# Programador_XILINX.net
KiCad netlist of a schematic drawn in Altium Designer
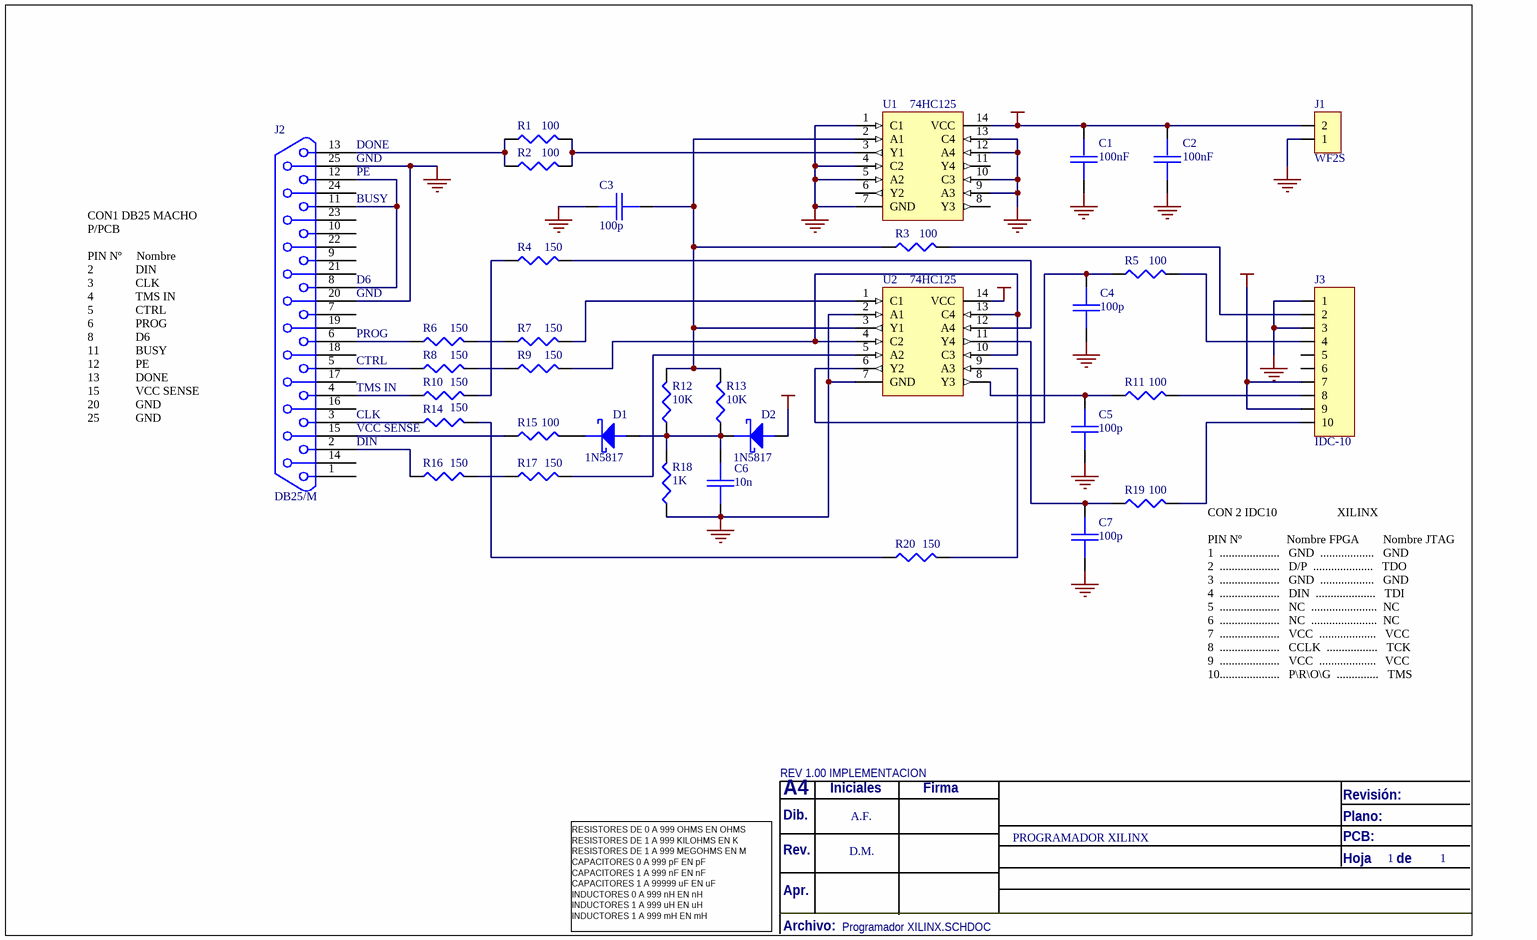
[diagram p0: Programador XILINX.SCHDOC]

(export (version "E")
  (design (tool "Eeschema 10.0.6"))
  (components
    (comp (ref "C1")
      (value "100nF")
      (footprint "0805")
      (description "CAPACITOR SMD 0805 X7R  50 V 100 nF")
      (libsource (lib "CAPACITORES SMD0805") (part "100n"))
    )
    (comp (ref "C2")
      (value "100nF")
      (footprint "0805")
      (description "CAPACITOR SMD 0805 X7R  50 V 100 nF")
      (libsource (lib "CAPACITORES SMD0805") (part "100n"))
    )
    (comp (ref "C3")
      (value "100p")
      (footprint "CAP2.54")
      (description "CAPACITOR CERAMICO DISCO 2.54 mm  X7R  50V  100pF")
      (libsource (lib "CAPACITORES CERAMICO DISCO") (part "100p"))
    )
    (comp (ref "C4")
      (value "100p")
      (footprint "CAP2.54")
      (description "CAPACITOR CERAMICO DISCO 2.54 mm  X7R  50V  100pF")
      (libsource (lib "CAPACITORES CERAMICO DISCO") (part "100p"))
    )
    (comp (ref "C5")
      (value "100p")
      (footprint "CAP2.54")
      (description "CAPACITOR CERAMICO DISCO 2.54 mm  X7R  50V  100pF")
      (libsource (lib "CAPACITORES CERAMICO DISCO") (part "100p"))
    )
    (comp (ref "C6")
      (value "10n")
      (footprint "CAP2.54")
      (description "CAPACITOR CERAMICO DISCO 2.54 mm  X7R  50V  10nF")
      (libsource (lib "CAPACITORES CERAMICO DISCO") (part "10n"))
    )
    (comp (ref "C7")
      (value "100p")
      (footprint "CAP2.54")
      (description "CAPACITOR CERAMICO DISCO 2.54 mm  X7R  50V  100pF")
      (libsource (lib "CAPACITORES CERAMICO DISCO") (part "100p"))
    )
    (comp (ref "D1")
      (value "1N5817")
      (footprint "DO-41_300")
      (description "DIODO SCHOTTKY 1N5817 DO-41")
      (libsource (lib "DIODOS") (part "1N5817 DO-41"))
    )
    (comp (ref "D2")
      (value "1N5817")
      (footprint "DO-41_300")
      (description "DIODO SCHOTTKY 1N5817 DO-41")
      (libsource (lib "DIODOS") (part "1N5817 DO-41"))
    )
    (comp (ref "J1")
      (value "WF2S")
      (footprint "WF2S")
      (description "WF2S HEADER .100\" RECTO 2 VIAS")
      (libsource (lib "CONECTORES") (part "WF2S"))
    )
    (comp (ref "J2")
      (value "DB25/M")
      (footprint "DB25 MACHO 90º")
      (description "DB25M CONECTOR D SUBMINIATURA 12 VIAS MACHO CABLE")
      (libsource (lib "CONECTORES") (part "DB25/M"))
    )
    (comp (ref "J3")
      (value "IDC-10")
      (footprint "IDC10")
      (description "CONECTOR IDC MACHO PCB NO POLARIZADO PASO 2.54 mm RECTO 2X5 VIAS")
      (libsource (lib "CONECTORES") (part "IDC10"))
    )
    (comp (ref "R1")
      (value "100")
      (footprint "RES_MF1/2W_200")
      (description "RESISTOR METAL FILM 0.5 W 5% 100 OHMS")
      (libsource (lib "RESISTORES METAL FILM MEDIO WATT") (part "100"))
    )
    (comp (ref "R2")
      (value "100")
      (footprint "RES_MF1/2W_200")
      (description "RESISTOR METAL FILM 0.5 W 5% 100 OHMS")
      (libsource (lib "RESISTORES METAL FILM MEDIO WATT") (part "100"))
    )
    (comp (ref "R3")
      (value "100")
      (footprint "RES_MF1/2W_200")
      (description "RESISTOR METAL FILM 0.5 W 5% 100 OHMS")
      (libsource (lib "RESISTORES METAL FILM MEDIO WATT") (part "100"))
    )
    (comp (ref "R4")
      (value "150")
      (footprint "RES_MF1/2W_200")
      (description "RESISTOR METAL FILM 0.5 W 5% 150 OHMS")
      (libsource (lib "RESISTORES METAL FILM MEDIO WATT") (part "150"))
    )
    (comp (ref "R5")
      (value "100")
      (footprint "RES_MF1/2W_200")
      (description "RESISTOR METAL FILM 0.5 W 5% 100 OHMS")
      (libsource (lib "RESISTORES METAL FILM MEDIO WATT") (part "100"))
    )
    (comp (ref "R6")
      (value "150")
      (footprint "RES_MF1/2W_200")
      (description "RESISTOR METAL FILM 0.5 W 5% 150 OHMS")
      (libsource (lib "RESISTORES METAL FILM MEDIO WATT") (part "150"))
    )
    (comp (ref "R7")
      (value "150")
      (footprint "RES_MF1/2W_200")
      (description "RESISTOR METAL FILM 0.5 W 5% 150 OHMS")
      (libsource (lib "RESISTORES METAL FILM MEDIO WATT") (part "150"))
    )
    (comp (ref "R8")
      (value "150")
      (footprint "RES_MF1/2W_200")
      (description "RESISTOR METAL FILM 0.5 W 5% 150 OHMS")
      (libsource (lib "RESISTORES METAL FILM MEDIO WATT") (part "150"))
    )
    (comp (ref "R9")
      (value "150")
      (footprint "RES_MF1/2W_200")
      (description "RESISTOR METAL FILM 0.5 W 5% 150 OHMS")
      (libsource (lib "RESISTORES METAL FILM MEDIO WATT") (part "150"))
    )
    (comp (ref "R10")
      (value "150")
      (footprint "RES_MF1/2W_200")
      (description "RESISTOR METAL FILM 0.5 W 5% 150 OHMS")
      (libsource (lib "RESISTORES METAL FILM MEDIO WATT") (part "150"))
    )
    (comp (ref "R11")
      (value "100")
      (footprint "RES_MF1/2W_200")
      (description "RESISTOR METAL FILM 0.5 W 5% 100 OHMS")
      (libsource (lib "RESISTORES METAL FILM MEDIO WATT") (part "100"))
    )
    (comp (ref "R12")
      (value "10K")
      (footprint "RES_MF1/2W_300")
      (description "RESISTOR METAL FILM 0.5 W 5% 10 KILOHMS")
      (libsource (lib "RESISTORES METAL FILM MEDIO WATT") (part "10K"))
    )
    (comp (ref "R13")
      (value "10K")
      (footprint "RES_MF1/2W_200")
      (description "RESISTOR METAL FILM 0.5 W 5% 10 KILOHMS")
      (libsource (lib "RESISTORES METAL FILM MEDIO WATT") (part "10K"))
    )
    (comp (ref "R14")
      (value "150")
      (footprint "RES_MF1/2W_200")
      (description "RESISTOR METAL FILM 0.5 W 5% 150 OHMS")
      (libsource (lib "RESISTORES METAL FILM MEDIO WATT") (part "150"))
    )
    (comp (ref "R15")
      (value "100")
      (footprint "RES_MF1/2W_200")
      (description "RESISTOR METAL FILM 0.5 W 5% 100 OHMS")
      (libsource (lib "RESISTORES METAL FILM MEDIO WATT") (part "100"))
    )
    (comp (ref "R16")
      (value "150")
      (footprint "RES_MF1/2W_200")
      (description "RESISTOR METAL FILM 0.5 W 5% 150 OHMS")
      (libsource (lib "RESISTORES METAL FILM MEDIO WATT") (part "150"))
    )
    (comp (ref "R17")
      (value "150")
      (footprint "RES_MF1/2W_200")
      (description "RESISTOR METAL FILM 0.5 W 5% 150 OHMS")
      (libsource (lib "RESISTORES METAL FILM MEDIO WATT") (part "150"))
    )
    (comp (ref "R18")
      (value "1K")
      (footprint "RES_MF1/2W_300")
      (description "RESISTOR METAL FILM 0.5 W 5% 1 K OHMS")
      (libsource (lib "RESISTORES METAL FILM MEDIO WATT") (part "1K"))
    )
    (comp (ref "R19")
      (value "100")
      (footprint "RES_MF1/2W_200")
      (description "RESISTOR METAL FILM 0.5 W 5% 100 OHMS")
      (libsource (lib "RESISTORES METAL FILM MEDIO WATT") (part "100"))
    )
    (comp (ref "R20")
      (value "150")
      (footprint "RES_MF1/2W_200")
      (description "RESISTOR METAL FILM 0.5 W 5% 150 OHMS")
      (libsource (lib "RESISTORES METAL FILM MEDIO WATT") (part "150"))
    )
    (comp (ref "U1")
      (value "74HC125")
      (footprint "DIP14")
      (description "QUAD 3-STATE NON INVERTING BUFFERS")
      (libsource (lib "CIRCUITOS INTEGRADOS DIP") (part "74HC125 DIP"))
    )
    (comp (ref "U2")
      (value "74HC125")
      (footprint "DIP14")
      (description "QUAD 3-STATE NON INVERTING BUFFERS")
      (libsource (lib "CIRCUITOS INTEGRADOS DIP") (part "74HC125 DIP"))
    )
  )
  (nets
    (net (code "1") (name "GND") (class "Default")
      (node (ref "C1") (pin "2") (pintype "passive"))
      (node (ref "C2") (pin "2") (pintype "passive"))
      (node (ref "C3") (pin "1") (pintype "passive"))
      (node (ref "C4") (pin "1") (pintype "passive"))
      (node (ref "C5") (pin "1") (pintype "passive"))
      (node (ref "C6") (pin "1") (pintype "passive"))
      (node (ref "C7") (pin "1") (pintype "passive"))
      (node (ref "J1") (pin "1") (pinfunction "1_1") (pintype "passive"))
      (node (ref "J2") (pin "20") (pintype "passive"))
      (node (ref "J2") (pin "25") (pintype "passive"))
      (node (ref "J3") (pin "1") (pinfunction "1_1") (pintype "passive"))
      (node (ref "J3") (pin "3") (pinfunction "3_3") (pintype "passive"))
      (node (ref "R18") (pin "1") (pintype "passive"))
      (node (ref "U1") (pin "1") (pinfunction "C1_1") (pintype "input"))
      (node (ref "U1") (pin "10") (pinfunction "C3_10") (pintype "input"))
      (node (ref "U1") (pin "12") (pinfunction "A4_12") (pintype "input"))
      (node (ref "U1") (pin "13") (pinfunction "C4_13") (pintype "input"))
      (node (ref "U1") (pin "4") (pinfunction "C2_4") (pintype "input"))
      (node (ref "U1") (pin "5") (pinfunction "A2_5") (pintype "input"))
      (node (ref "U1") (pin "7") (pinfunction "GND_7") (pintype "power_in"))
      (node (ref "U1") (pin "9") (pinfunction "A3_9") (pintype "input"))
      (node (ref "U2") (pin "2") (pinfunction "A1_2") (pintype "input"))
      (node (ref "U2") (pin "7") (pinfunction "GND_7") (pintype "power_in"))
    )
    (net (code "2") (name "Net-(C6-Pad2)") (class "Default")
      (node (ref "C6") (pin "2") (pintype "passive"))
      (node (ref "D1") (pin "A") (pinfunction "A_A") (pintype "passive"))
      (node (ref "D2") (pin "K") (pinfunction "K_K") (pintype "passive"))
      (node (ref "R12") (pin "1") (pintype "passive"))
      (node (ref "R13") (pin "1") (pintype "passive"))
      (node (ref "R18") (pin "2") (pintype "passive"))
    )
    (net (code "3") (name "Net-(D1-PadK)") (class "Default")
      (node (ref "D1") (pin "K") (pinfunction "K_K") (pintype "passive"))
      (node (ref "R15") (pin "2") (pintype "passive"))
    )
    (net (code "4") (name "Net-(J2-Pad2)") (class "Default")
      (node (ref "J2") (pin "2") (pintype "passive"))
      (node (ref "R16") (pin "1") (pintype "passive"))
    )
    (net (code "5") (name "Net-(J2-Pad3)") (class "Default")
      (node (ref "J2") (pin "3") (pintype "passive"))
      (node (ref "R14") (pin "1") (pintype "passive"))
    )
    (net (code "6") (name "Net-(J2-Pad4)") (class "Default")
      (node (ref "J2") (pin "4") (pintype "passive"))
      (node (ref "R10") (pin "1") (pintype "passive"))
    )
    (net (code "7") (name "Net-(J2-Pad5)") (class "Default")
      (node (ref "J2") (pin "5") (pintype "passive"))
      (node (ref "R8") (pin "1") (pintype "passive"))
    )
    (net (code "8") (name "Net-(J2-Pad6)") (class "Default")
      (node (ref "J2") (pin "6") (pintype "passive"))
      (node (ref "R6") (pin "1") (pintype "passive"))
    )
    (net (code "9") (name "Net-(J2-Pad11)") (class "Default")
      (node (ref "J2") (pin "11") (pintype "passive"))
      (node (ref "J2") (pin "12") (pintype "passive"))
      (node (ref "J2") (pin "8") (pintype "passive"))
    )
    (net (code "10") (name "Net-(J2-Pad13)") (class "Default")
      (node (ref "J2") (pin "13") (pintype "passive"))
      (node (ref "R1") (pin "1") (pintype "passive"))
      (node (ref "R2") (pin "1") (pintype "passive"))
    )
    (net (code "11") (name "Net-(J2-Pad15)") (class "Default")
      (node (ref "J2") (pin "15") (pintype "passive"))
      (node (ref "R15") (pin "1") (pintype "passive"))
    )
    (net (code "12") (name "Net-(J3-Pad2)") (class "Default")
      (node (ref "J3") (pin "2") (pinfunction "2_2") (pintype "passive"))
      (node (ref "R3") (pin "2") (pintype "passive"))
    )
    (net (code "13") (name "Net-(J3-Pad4)") (class "Default")
      (node (ref "J3") (pin "4") (pinfunction "4_4") (pintype "passive"))
      (node (ref "R5") (pin "2") (pintype "passive"))
    )
    (net (code "14") (name "Net-(J3-Pad8)") (class "Default")
      (node (ref "J3") (pin "8") (pinfunction "8_8") (pintype "passive"))
      (node (ref "R11") (pin "2") (pintype "passive"))
    )
    (net (code "15") (name "Net-(J3-Pad10)") (class "Default")
      (node (ref "J3") (pin "10") (pinfunction "10_10") (pintype "passive"))
      (node (ref "R19") (pin "2") (pintype "passive"))
    )
    (net (code "16") (name "Net-(R6-Pad2)") (class "Default")
      (node (ref "R6") (pin "2") (pintype "passive"))
      (node (ref "R7") (pin "1") (pintype "passive"))
    )
    (net (code "17") (name "Net-(R8-Pad2)") (class "Default")
      (node (ref "R8") (pin "2") (pintype "passive"))
      (node (ref "R9") (pin "1") (pintype "passive"))
    )
    (net (code "18") (name "Net-(R10-Pad2)") (class "Default")
      (node (ref "R10") (pin "2") (pintype "passive"))
      (node (ref "R4") (pin "1") (pintype "passive"))
    )
    (net (code "19") (name "Net-(R14-Pad2)") (class "Default")
      (node (ref "R14") (pin "2") (pintype "passive"))
      (node (ref "R20") (pin "1") (pintype "passive"))
    )
    (net (code "20") (name "Net-(R16-Pad2)") (class "Default")
      (node (ref "R16") (pin "2") (pintype "passive"))
      (node (ref "R17") (pin "1") (pintype "passive"))
    )
    (net (code "21") (name "Net-(U1-A1)") (class "Default")
      (node (ref "C3") (pin "2") (pintype "passive"))
      (node (ref "R12") (pin "2") (pintype "passive"))
      (node (ref "R13") (pin "2") (pintype "passive"))
      (node (ref "R3") (pin "1") (pintype "passive"))
      (node (ref "U1") (pin "2") (pinfunction "A1_2") (pintype "input"))
      (node (ref "U2") (pin "3") (pinfunction "Y1_3") (pintype "output"))
    )
    (net (code "22") (name "Net-(U1-Y1)") (class "Default")
      (node (ref "R1") (pin "2") (pintype "passive"))
      (node (ref "R2") (pin "2") (pintype "passive"))
      (node (ref "U1") (pin "3") (pinfunction "Y1_3") (pintype "output"))
    )
    (net (code "23") (name "Net-(U2-A2)") (class "Default")
      (node (ref "R17") (pin "2") (pintype "passive"))
      (node (ref "U2") (pin "5") (pinfunction "A2_5") (pintype "input"))
    )
    (net (code "24") (name "Net-(U2-A3)") (class "Default")
      (node (ref "R20") (pin "2") (pintype "passive"))
      (node (ref "U2") (pin "9") (pinfunction "A3_9") (pintype "input"))
    )
    (net (code "25") (name "Net-(U2-A4)") (class "Default")
      (node (ref "R4") (pin "2") (pintype "passive"))
      (node (ref "U2") (pin "12") (pinfunction "A4_12") (pintype "input"))
    )
    (net (code "26") (name "Net-(U2-C1)") (class "Default")
      (node (ref "R7") (pin "2") (pintype "passive"))
      (node (ref "U2") (pin "1") (pinfunction "C1_1") (pintype "input"))
    )
    (net (code "27") (name "Net-(U2-C2)") (class "Default")
      (node (ref "R9") (pin "2") (pintype "passive"))
      (node (ref "U2") (pin "10") (pinfunction "C3_10") (pintype "input"))
      (node (ref "U2") (pin "13") (pinfunction "C4_13") (pintype "input"))
      (node (ref "U2") (pin "4") (pinfunction "C2_4") (pintype "input"))
    )
    (net (code "28") (name "Net-(U2-Y2)") (class "Default")
      (node (ref "C4") (pin "2") (pintype "passive"))
      (node (ref "R5") (pin "1") (pintype "passive"))
      (node (ref "U2") (pin "6") (pinfunction "Y2_6") (pintype "output"))
    )
    (net (code "29") (name "Net-(U2-Y3)") (class "Default")
      (node (ref "C5") (pin "2") (pintype "passive"))
      (node (ref "R11") (pin "1") (pintype "passive"))
      (node (ref "U2") (pin "8") (pinfunction "Y3_8") (pintype "output"))
    )
    (net (code "30") (name "Net-(U2-Y4)") (class "Default")
      (node (ref "C7") (pin "2") (pintype "passive"))
      (node (ref "R19") (pin "1") (pintype "passive"))
      (node (ref "U2") (pin "11") (pinfunction "Y4_11") (pintype "output"))
    )
    (net (code "31") (name "VCC") (class "Default")
      (node (ref "C1") (pin "1") (pintype "passive"))
      (node (ref "C2") (pin "1") (pintype "passive"))
      (node (ref "D2") (pin "A") (pinfunction "A_A") (pintype "passive"))
      (node (ref "J1") (pin "2") (pinfunction "2_2") (pintype "passive"))
      (node (ref "J3") (pin "7") (pinfunction "7_7") (pintype "passive"))
      (node (ref "J3") (pin "9") (pinfunction "9_9") (pintype "passive"))
      (node (ref "U1") (pin "14") (pinfunction "VCC_14") (pintype "power_in"))
      (node (ref "U2") (pin "14") (pinfunction "VCC_14") (pintype "power_in"))
    )
    (net (code "32") (name "unconnected-(J2-Pad1)") (class "Default")
      (node (ref "J2") (pin "1") (pintype "passive"))
    )
    (net (code "33") (name "unconnected-(J2-Pad7)") (class "Default")
      (node (ref "J2") (pin "7") (pintype "passive"))
    )
    (net (code "34") (name "unconnected-(J2-Pad9)") (class "Default")
      (node (ref "J2") (pin "9") (pintype "passive"))
    )
    (net (code "35") (name "unconnected-(J2-Pad10)") (class "Default")
      (node (ref "J2") (pin "10") (pintype "passive"))
    )
    (net (code "36") (name "unconnected-(J2-Pad14)") (class "Default")
      (node (ref "J2") (pin "14") (pintype "passive"))
    )
    (net (code "37") (name "unconnected-(J2-Pad16)") (class "Default")
      (node (ref "J2") (pin "16") (pintype "passive"))
    )
    (net (code "38") (name "unconnected-(J2-Pad17)") (class "Default")
      (node (ref "J2") (pin "17") (pintype "passive"))
    )
    (net (code "39") (name "unconnected-(J2-Pad18)") (class "Default")
      (node (ref "J2") (pin "18") (pintype "passive"))
    )
    (net (code "40") (name "unconnected-(J2-Pad19)") (class "Default")
      (node (ref "J2") (pin "19") (pintype "passive"))
    )
    (net (code "41") (name "unconnected-(J2-Pad21)") (class "Default")
      (node (ref "J2") (pin "21") (pintype "passive"))
    )
    (net (code "42") (name "unconnected-(J2-Pad22)") (class "Default")
      (node (ref "J2") (pin "22") (pintype "passive"))
    )
    (net (code "43") (name "unconnected-(J2-Pad23)") (class "Default")
      (node (ref "J2") (pin "23") (pintype "passive"))
    )
    (net (code "44") (name "unconnected-(J2-Pad24)") (class "Default")
      (node (ref "J2") (pin "24") (pintype "passive"))
    )
    (net (code "45") (name "unconnected-(J3-5-Pad)") (class "Default")
      (node (ref "J3") (pin "") (pinfunction "5_") (pintype "passive"))
    )
    (net (code "46") (name "unconnected-(J3-6-Pad)") (class "Default")
      (node (ref "J3") (pin "") (pinfunction "6_") (pintype "passive"))
    )
    (net (code "47") (name "unconnected-(U1-Y2-Pad6)") (class "Default")
      (node (ref "U1") (pin "6") (pinfunction "Y2_6") (pintype "output"))
    )
    (net (code "48") (name "unconnected-(U1-Y3-Pad8)") (class "Default")
      (node (ref "U1") (pin "8") (pinfunction "Y3_8") (pintype "output"))
    )
    (net (code "49") (name "unconnected-(U1-Y4-Pad11)") (class "Default")
      (node (ref "U1") (pin "11") (pinfunction "Y4_11") (pintype "output"))
    )
  )
)
